# 20260908.net
KiCad netlist of a schematic drawn in Altium Designer
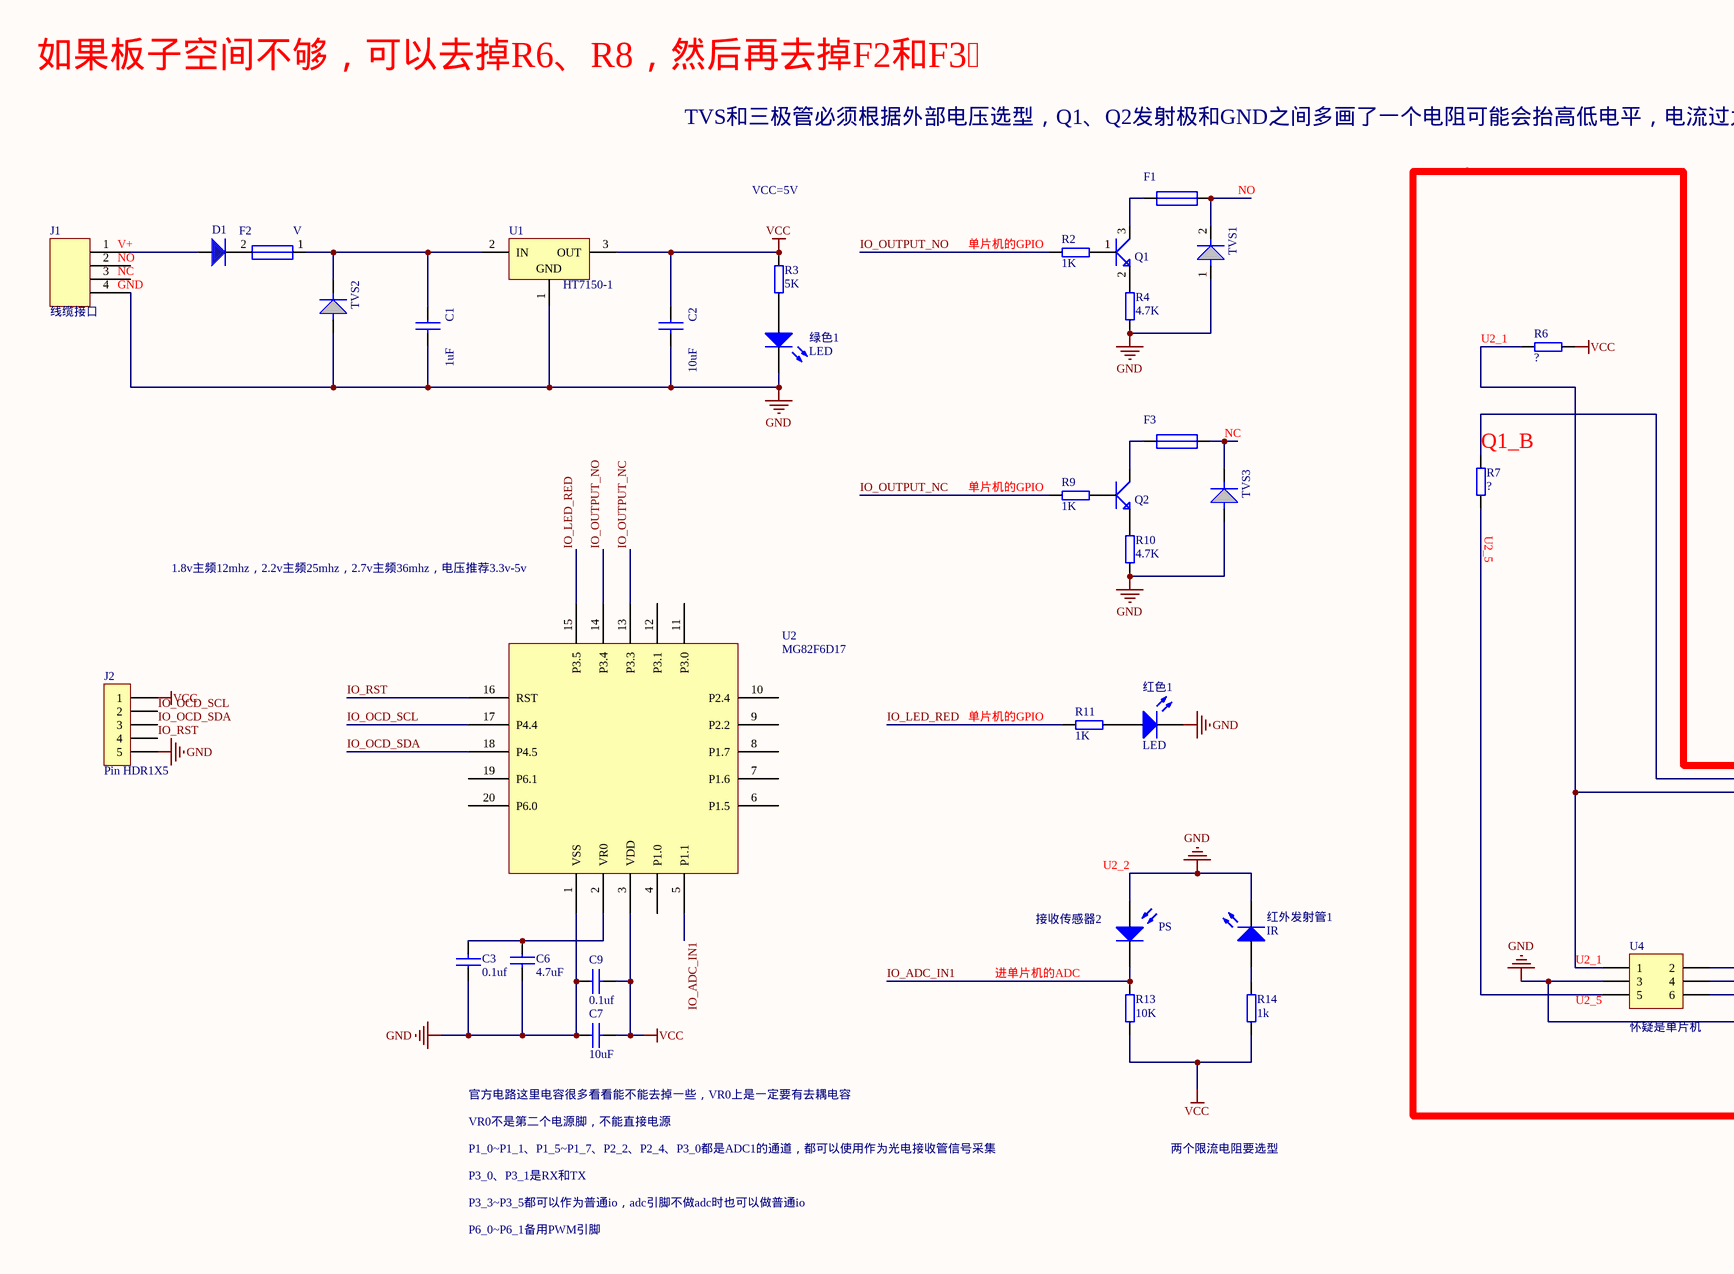
[diagram p0: 槽形开关原理图20260908.SchDoc, left]
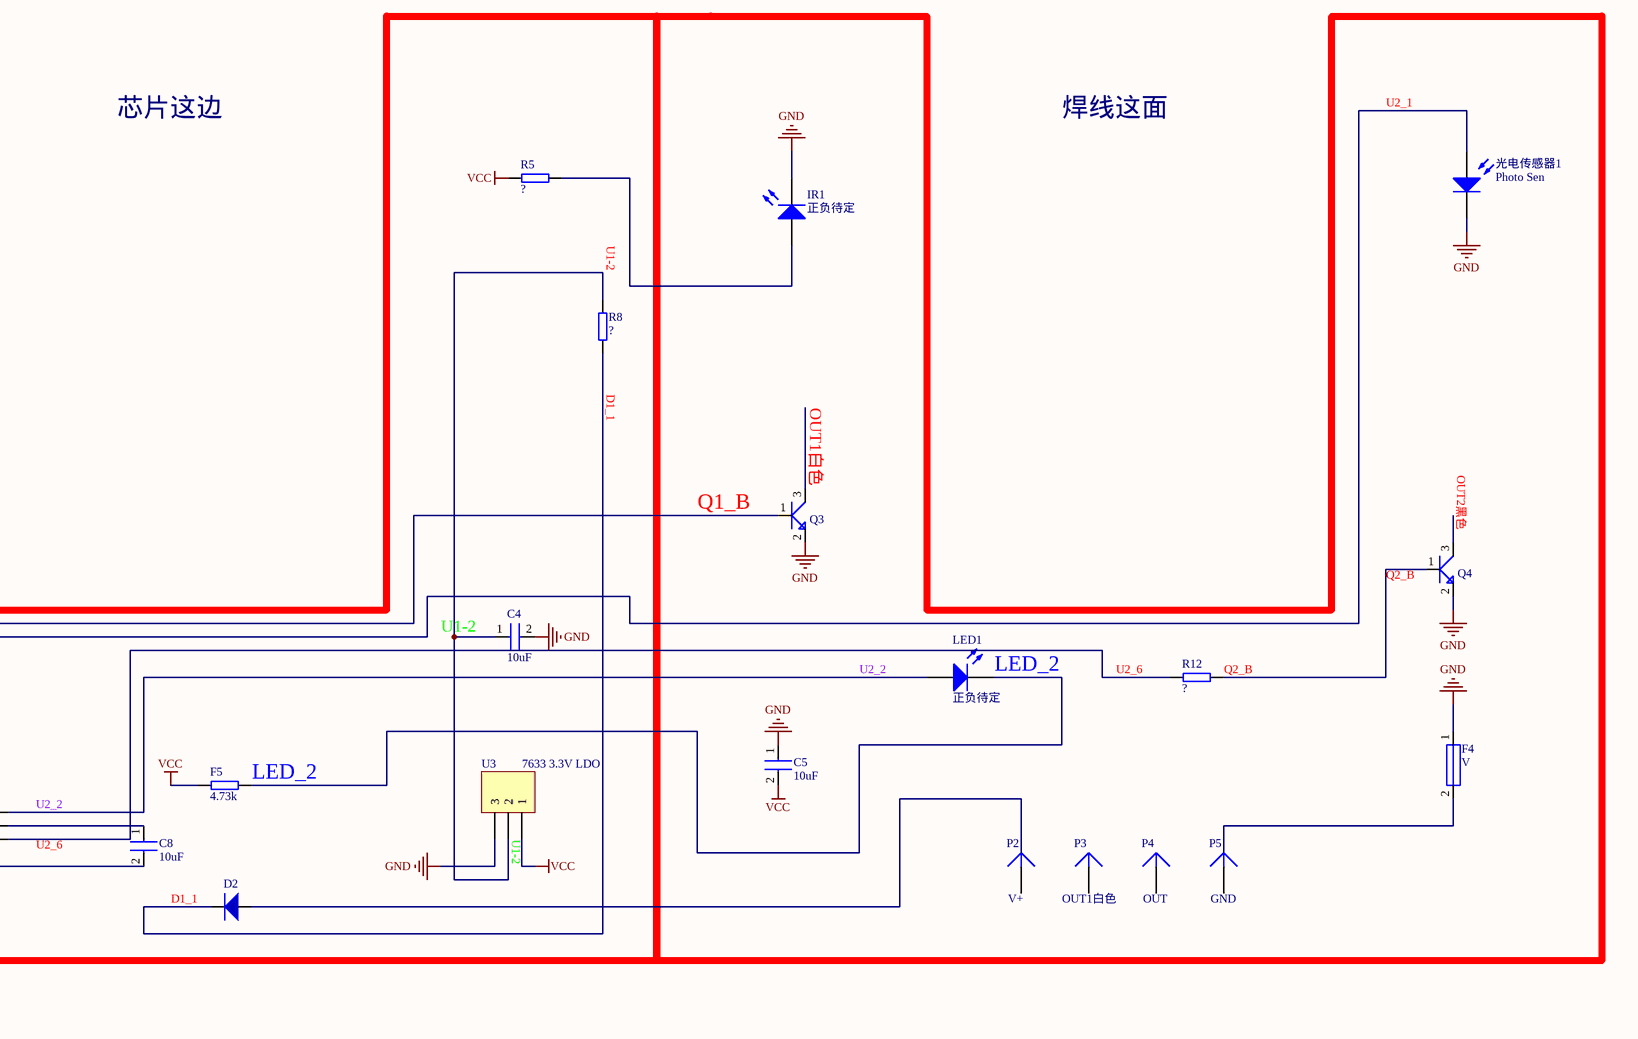
[diagram p1: 槽形开关原理图20260908.SchDoc, right]

(export (version "E")
  (design (tool "Eeschema 10.0.6"))
  (components
    (comp (ref "C1") (value "1uF") (footprint "1206") (libsource (lib "*") (part "CAP NP")))
    (comp (ref "C2") (value "10uF") (footprint "1206") (libsource (lib "*") (part "CAP NP")))
    (comp (ref "C3") (value "0.1uf") (footprint "1206") (libsource (lib "*") (part "CAP NP")))
    (comp (ref "C4") (value "10uF") (libsource (lib "*") (part "CAP")))
    (comp (ref "C5") (value "10uF") (libsource (lib "*") (part "CAP")))
    (comp (ref "C6") (value "4.7uF") (footprint "1206") (libsource (lib "*") (part "CAP NP")))
    (comp (ref "C7") (value "10uF") (footprint "1206") (libsource (lib "*") (part "CAP NP")))
    (comp (ref "C8") (value "10uF") (libsource (lib "*") (part "CAP")))
    (comp (ref "C9") (value "0.1uf") (footprint "1206") (libsource (lib "*") (part "CAP NP")))
    (comp (ref "D1") (value "~") (libsource (lib "*") (part "D")))
    (comp (ref "D2") (value "~") (libsource (lib "*") (part "D")))
    (comp (ref "F1") (value "V") (footprint "0805") (libsource (lib "") (part "FUSE_0_1")))
    (comp (ref "F2") (value "V") (footprint "0805") (libsource (lib "*") (part "FUSE_0")))
    (comp (ref "F3") (value "~") (footprint "0805") (libsource (lib "") (part "FUSE_0_1")))
    (comp (ref "F4") (value "V") (footprint "0805") (libsource (lib "") (part "FUSE_0_2")))
    (comp (ref "F5") (value "4.73k") (libsource (lib "*") (part "RES")))
    (comp (ref "IR1")
      (value "正负待定")
      (footprint "LED-0")
      (description "Typical INFRARED GaAs LED")
      (fields (field (name "PUBLISHER") "Altium Limited"))
      (libsource (lib "Miscellaneous Devices") (part "LED0"))
    )
    (comp (ref "J1") (value "线缆接口") (footprint "SIP4") (libsource (lib "*") (part "4H")))
    (comp (ref "J2")
      (value "Pin HDR1X5")
      (footprint "Pin HDR1X5/2mm-W")
      (libsource (lib "排针") (part "Pin HDR1X5"))
    )
    (comp (ref "LED1")
      (value "正负待定")
      (footprint "LED-0")
      (description "Typical INFRARED GaAs LED")
      (fields (field (name "PUBLISHER") "Altium Limited"))
      (libsource (lib "Miscellaneous Devices") (part "LED0"))
    )
    (comp (ref "P2")
      (value "V+")
      (footprint "PIN1")
      (description "Plug")
      (fields (field (name "PUBLISHER") "Altium Limited"))
      (libsource (lib "Miscellaneous Connectors") (part "Plug"))
    )
    (comp (ref "P3")
      (value "OUT1白色")
      (footprint "PIN1")
      (description "Plug")
      (fields (field (name "PUBLISHER") "Altium Limited"))
      (libsource (lib "Miscellaneous Connectors") (part "Plug"))
    )
    (comp (ref "P4")
      (value "OUT")
      (footprint "PIN1")
      (description "Plug")
      (fields (field (name "PUBLISHER") "Altium Limited"))
      (libsource (lib "Miscellaneous Connectors") (part "Plug"))
    )
    (comp (ref "P5")
      (value "GND")
      (footprint "PIN1")
      (description "Plug")
      (fields (field (name "PUBLISHER") "Altium Limited"))
      (libsource (lib "Miscellaneous Connectors") (part "Plug"))
    )
    (comp (ref "Q1") (value "2SC4617TLR") (libsource (lib "") (part "2SC4617_1")))
    (comp (ref "Q2") (value "2SC4617TLR") (libsource (lib "*") (part "2SC4617")))
    (comp (ref "Q3") (value "2SC4617TLR") (libsource (lib "") (part "2SC4617_1")))
    (comp (ref "Q4") (value "2SC4617TLR") (libsource (lib "") (part "2SC4617_1")))
    (comp (ref "R2") (value "1K") (libsource (lib "*") (part "RES")))
    (comp (ref "R3") (value "5K") (libsource (lib "*") (part "RES")))
    (comp (ref "R4") (value "4.7K") (libsource (lib "*") (part "RES")))
    (comp (ref "R5") (value "?") (libsource (lib "*") (part "RES")))
    (comp (ref "R6") (value "?") (libsource (lib "*") (part "RES")))
    (comp (ref "R7") (value "?") (libsource (lib "*") (part "RES")))
    (comp (ref "R8") (value "?") (libsource (lib "*") (part "RES")))
    (comp (ref "R9") (value "1K") (libsource (lib "*") (part "RES")))
    (comp (ref "R10") (value "4.7K") (libsource (lib "*") (part "RES")))
    (comp (ref "R11") (value "1K") (libsource (lib "*") (part "RES")))
    (comp (ref "R12") (value "?") (libsource (lib "*") (part "RES")))
    (comp (ref "R13") (value "10K") (libsource (lib "*") (part "RES")))
    (comp (ref "R14") (value "1k") (libsource (lib "*") (part "RES")))
    (comp (ref "TVS1") (value "~") (footprint "1206") (libsource (lib "") (part "D1N3063_0_1")))
    (comp (ref "TVS2") (value "M1") (footprint "1206") (libsource (lib "*") (part "D1N3063_0")))
    (comp (ref "TVS3") (value "~") (footprint "1206") (libsource (lib "*") (part "D1N3063_0")))
    (comp (ref "U1")
      (value "HT7150-1")
      (footprint "SOT89N")
      (description "3.0V 100mA Low Power,  Low Dropout Voltage (LDO) Regulator")
      (fields (field (name "PUBLISHER") "Altium Limited"))
      (libsource (lib "Holtek Power Mgt Voltage Regulator") (part "HT7530-1"))
    )
    (comp (ref "U2") (value "MG82F6D17") (libsource (lib "wwrDevice") (part "MG82F6D17 QFN20")))
    (comp (ref "U3")
      (value "7633 3.3V LDO")
      (footprint "HDR1X3")
      (description "Header, 3-Pin")
      (fields (field (name "PUBLISHER") "Altium Limited"))
      (libsource (lib "Miscellaneous Connectors") (part "Header 3"))
    )
    (comp (ref "U4")
      (value "怀疑是单片机")
      (footprint "HDR2X3")
      (description "Header, 3-Pin, Dual row")
      (fields (field (name "PUBLISHER") "Altium Limited"))
      (libsource (lib "Miscellaneous Connectors") (part "Header 3X2"))
    )
    (comp (ref "光电传感器1")
      (value "Photo Sen")
      (footprint "PIN2")
      (description "Photosensitive Diode")
      (fields (field (name "PUBLISHER") "Altium Limited"))
      (libsource (lib "Miscellaneous Devices") (part "Photo Sen"))
    )
    (comp (ref "接收传感器2")
      (value "PS")
      (footprint "PIN2")
      (description "Photosensitive Diode")
      (fields (field (name "PUBLISHER") "Altium Limited"))
      (libsource (lib "Miscellaneous Devices") (part "Photo Sen"))
    )
    (comp (ref "红外发射管1")
      (value "IR")
      (footprint "LED-0")
      (description "Typical INFRARED GaAs LED")
      (fields (field (name "PUBLISHER") "Altium Limited"))
      (libsource (lib "Miscellaneous Devices") (part "LED0"))
    )
    (comp (ref "红色1")
      (value "LED")
      (footprint "LED-0")
      (description "Typical INFRARED GaAs LED")
      (fields (field (name "PUBLISHER") "Altium Limited"))
      (libsource (lib "Miscellaneous Devices") (part "LED0"))
    )
    (comp (ref "绿色1")
      (value "LED")
      (footprint "LED-0")
      (description "Typical INFRARED GaAs LED")
      (fields (field (name "PUBLISHER") "Altium Limited"))
      (libsource (lib "Miscellaneous Devices") (part "LED0"))
    )
  )
  (nets
    (net (code "1") (name "/IO_ADC_IN1") (class "Default")
      (node (ref "R13") (pin "2") (pinfunction "2_2") (pintype "passive"))
      (node (ref "U2") (pin "5") (pinfunction "P1.1_5") (pintype "passive"))
      (node (ref "接收传感器2") (pin "2") (pinfunction "K_2") (pintype "passive"))
    )
    (net (code "2") (name "/IO_LED_RED") (class "Default")
      (node (ref "R11") (pin "1") (pinfunction "1_1") (pintype "passive"))
      (node (ref "U2") (pin "15") (pinfunction "P3.5_15") (pintype "passive"))
    )
    (net (code "3") (name "/IO_OCD_SCL") (class "Default")
      (node (ref "J2") (pin "2") (pinfunction "2_2") (pintype "passive"))
      (node (ref "U2") (pin "17") (pinfunction "P4.4_17") (pintype "passive"))
    )
    (net (code "4") (name "/IO_OCD_SDA") (class "Default")
      (node (ref "J2") (pin "3") (pinfunction "3_3") (pintype "passive"))
      (node (ref "U2") (pin "18") (pinfunction "P4.5_18") (pintype "passive"))
    )
    (net (code "5") (name "/IO_OUTPUT_NC") (class "Default")
      (node (ref "R9") (pin "1") (pinfunction "1_1") (pintype "passive"))
      (node (ref "U2") (pin "13") (pinfunction "P3.3_13") (pintype "passive"))
    )
    (net (code "6") (name "/IO_OUTPUT_NO") (class "Default")
      (node (ref "R2") (pin "1") (pinfunction "1_1") (pintype "passive"))
      (node (ref "U2") (pin "14") (pinfunction "P3.4_14") (pintype "passive"))
    )
    (net (code "7") (name "/IO_RST") (class "Default")
      (node (ref "J2") (pin "4") (pinfunction "4_4") (pintype "passive"))
      (node (ref "U2") (pin "16") (pinfunction "RST_16") (pintype "passive"))
    )
    (net (code "8") (name "GND") (class "Default")
      (node (ref "C1") (pin "2") (pinfunction "2_2") (pintype "passive"))
      (node (ref "C2") (pin "2") (pinfunction "2_2") (pintype "passive"))
      (node (ref "C3") (pin "1") (pinfunction "1_1") (pintype "passive"))
      (node (ref "C4") (pin "2") (pintype "passive"))
      (node (ref "C5") (pin "1") (pintype "passive"))
      (node (ref "C6") (pin "2") (pinfunction "2_2") (pintype "passive"))
      (node (ref "C7") (pin "1") (pinfunction "1_1") (pintype "passive"))
      (node (ref "C8") (pin "2") (pintype "passive"))
      (node (ref "C9") (pin "1") (pinfunction "1_1") (pintype "passive"))
      (node (ref "F4") (pin "1") (pinfunction "1_1") (pintype "passive"))
      (node (ref "IR1") (pin "2") (pinfunction "K_2") (pintype "passive"))
      (node (ref "J1") (pin "4") (pintype "passive"))
      (node (ref "J2") (pin "5") (pinfunction "5_5") (pintype "passive"))
      (node (ref "Q3") (pin "2") (pinfunction "E_2") (pintype "passive"))
      (node (ref "Q4") (pin "2") (pinfunction "E_2") (pintype "passive"))
      (node (ref "R10") (pin "2") (pinfunction "2_2") (pintype "passive"))
      (node (ref "R4") (pin "2") (pinfunction "2_2") (pintype "passive"))
      (node (ref "TVS1") (pin "1") (pinfunction "1_1") (pintype "passive"))
      (node (ref "TVS2") (pin "1") (pinfunction "1_1") (pintype "passive"))
      (node (ref "TVS3") (pin "1") (pinfunction "1_1") (pintype "passive"))
      (node (ref "U1") (pin "1") (pinfunction "GND_1") (pintype "power_in"))
      (node (ref "U2") (pin "1") (pinfunction "VSS_1") (pintype "passive"))
      (node (ref "U3") (pin "3") (pinfunction "3_3") (pintype "passive"))
      (node (ref "U4") (pin "3") (pinfunction "3_3") (pintype "passive"))
      (node (ref "光电传感器1") (pin "2") (pinfunction "K_2") (pintype "passive"))
      (node (ref "接收传感器2") (pin "1") (pinfunction "A_1") (pintype "passive"))
      (node (ref "红外发射管1") (pin "2") (pinfunction "K_2") (pintype "passive"))
      (node (ref "红色1") (pin "2") (pinfunction "K_2") (pintype "passive"))
      (node (ref "绿色1") (pin "2") (pinfunction "K_2") (pintype "passive"))
    )
    (net (code "9") (name "Net-(C4-Pad1)") (class "Default")
      (node (ref "C4") (pin "1") (pintype "passive"))
      (node (ref "R8") (pin "2") (pinfunction "2_2") (pintype "passive"))
      (node (ref "U3") (pin "2") (pinfunction "2_2") (pintype "passive"))
    )
    (net (code "10") (name "Net-(C8-Pad1)") (class "Default")
      (node (ref "C8") (pin "1") (pintype "passive"))
      (node (ref "U4") (pin "4") (pinfunction "4_4") (pintype "passive"))
    )
    (net (code "11") (name "Net-(D1-Pad1)") (class "Default")
      (node (ref "D1") (pin "1") (pintype "passive"))
      (node (ref "J1") (pin "1") (pintype "passive"))
    )
    (net (code "12") (name "Net-(D1-Pad2)") (class "Default")
      (node (ref "D1") (pin "2") (pintype "passive"))
      (node (ref "F2") (pin "2") (pinfunction "2_2") (pintype "passive"))
    )
    (net (code "13") (name "Net-(D2-Pad2)") (class "Default")
      (node (ref "D2") (pin "2") (pintype "passive"))
      (node (ref "R8") (pin "1") (pinfunction "1_1") (pintype "passive"))
    )
    (net (code "14") (name "Net-(F1-Pad1)") (class "Default")
      (node (ref "F1") (pin "1") (pinfunction "1_1") (pintype "passive"))
      (node (ref "TVS1") (pin "2") (pinfunction "2_2") (pintype "passive"))
    )
    (net (code "15") (name "Net-(F3-Pad1)") (class "Default")
      (node (ref "F3") (pin "1") (pinfunction "1_1") (pintype "passive"))
      (node (ref "TVS3") (pin "2") (pinfunction "2_2") (pintype "passive"))
    )
    (net (code "16") (name "Net-(IR1-A)") (class "Default")
      (node (ref "IR1") (pin "1") (pinfunction "A_1") (pintype "passive"))
      (node (ref "R5") (pin "1") (pinfunction "1_1") (pintype "passive"))
    )
    (net (code "17") (name "Net-(LED1-A)") (class "Default")
      (node (ref "LED1") (pin "1") (pinfunction "A_1") (pintype "passive"))
      (node (ref "U4") (pin "2") (pinfunction "2_2") (pintype "passive"))
    )
    (net (code "18") (name "Net-(LED1-K)") (class "Default")
      (node (ref "F5") (pin "1") (pinfunction "1_1") (pintype "passive"))
      (node (ref "LED1") (pin "2") (pinfunction "K_2") (pintype "passive"))
    )
    (net (code "19") (name "Net-(Q1-B)") (class "Default")
      (node (ref "Q1") (pin "1") (pinfunction "B_1") (pintype "passive"))
      (node (ref "R2") (pin "2") (pinfunction "2_2") (pintype "passive"))
    )
    (net (code "20") (name "Net-(Q1-C)") (class "Default")
      (node (ref "F1") (pin "2") (pinfunction "2_2") (pintype "passive"))
      (node (ref "Q1") (pin "3") (pinfunction "C_3") (pintype "passive"))
    )
    (net (code "21") (name "Net-(Q1-E)") (class "Default")
      (node (ref "Q1") (pin "2") (pinfunction "E_2") (pintype "passive"))
      (node (ref "R4") (pin "1") (pinfunction "1_1") (pintype "passive"))
    )
    (net (code "22") (name "Net-(Q2-B)") (class "Default")
      (node (ref "Q2") (pin "1") (pinfunction "B_1") (pintype "passive"))
      (node (ref "R9") (pin "2") (pinfunction "2_2") (pintype "passive"))
    )
    (net (code "23") (name "Net-(Q2-C)") (class "Default")
      (node (ref "F3") (pin "2") (pinfunction "2_2") (pintype "passive"))
      (node (ref "Q2") (pin "3") (pinfunction "C_3") (pintype "passive"))
    )
    (net (code "24") (name "Net-(Q2-E)") (class "Default")
      (node (ref "Q2") (pin "2") (pinfunction "E_2") (pintype "passive"))
      (node (ref "R10") (pin "1") (pinfunction "1_1") (pintype "passive"))
    )
    (net (code "25") (name "Net-(Q3-B)") (class "Default")
      (node (ref "Q3") (pin "1") (pinfunction "B_1") (pintype "passive"))
      (node (ref "R7") (pin "2") (pinfunction "2_2") (pintype "passive"))
    )
    (net (code "26") (name "Net-(Q4-B)") (class "Default")
      (node (ref "Q4") (pin "1") (pinfunction "B_1") (pintype "passive"))
      (node (ref "R12") (pin "1") (pinfunction "1_1") (pintype "passive"))
    )
    (net (code "27") (name "Net-(R7-Pad1)") (class "Default")
      (node (ref "R7") (pin "1") (pinfunction "1_1") (pintype "passive"))
      (node (ref "U4") (pin "5") (pinfunction "5_5") (pintype "passive"))
    )
    (net (code "28") (name "Net-(R12-Pad2)") (class "Default")
      (node (ref "R12") (pin "2") (pinfunction "2_2") (pintype "passive"))
      (node (ref "U4") (pin "6") (pinfunction "6_6") (pintype "passive"))
    )
    (net (code "29") (name "Net-(U1-IN)") (class "Default")
      (node (ref "C1") (pin "1") (pinfunction "1_1") (pintype "passive"))
      (node (ref "F2") (pin "1") (pinfunction "1_1") (pintype "passive"))
      (node (ref "TVS2") (pin "2") (pinfunction "2_2") (pintype "passive"))
      (node (ref "U1") (pin "2") (pinfunction "IN_2") (pintype "power_in"))
    )
    (net (code "30") (name "Net-(U2-VR0)") (class "Default")
      (node (ref "C3") (pin "2") (pinfunction "2_2") (pintype "passive"))
      (node (ref "C6") (pin "1") (pinfunction "1_1") (pintype "passive"))
      (node (ref "U2") (pin "2") (pinfunction "VR0_2") (pintype "passive"))
    )
    (net (code "31") (name "Net-(光电传感器1-A)") (class "Default")
      (node (ref "R6") (pin "2") (pinfunction "2_2") (pintype "passive"))
      (node (ref "U4") (pin "1") (pinfunction "1_1") (pintype "passive"))
      (node (ref "光电传感器1") (pin "1") (pinfunction "A_1") (pintype "passive"))
    )
    (net (code "32") (name "Net-(红外发射管1-A)") (class "Default")
      (node (ref "R14") (pin "2") (pinfunction "2_2") (pintype "passive"))
      (node (ref "红外发射管1") (pin "1") (pinfunction "A_1") (pintype "passive"))
    )
    (net (code "33") (name "Net-(红色1-A)") (class "Default")
      (node (ref "R11") (pin "2") (pinfunction "2_2") (pintype "passive"))
      (node (ref "红色1") (pin "1") (pinfunction "A_1") (pintype "passive"))
    )
    (net (code "34") (name "Net-(绿色1-A)") (class "Default")
      (node (ref "R3") (pin "2") (pinfunction "2_2") (pintype "passive"))
      (node (ref "绿色1") (pin "1") (pinfunction "A_1") (pintype "passive"))
    )
    (net (code "35") (name "VCC") (class "Default")
      (node (ref "C2") (pin "1") (pinfunction "1_1") (pintype "passive"))
      (node (ref "C5") (pin "2") (pintype "passive"))
      (node (ref "C7") (pin "2") (pinfunction "2_2") (pintype "passive"))
      (node (ref "C9") (pin "2") (pinfunction "2_2") (pintype "passive"))
      (node (ref "F5") (pin "2") (pinfunction "2_2") (pintype "passive"))
      (node (ref "J2") (pin "1") (pinfunction "1_1") (pintype "passive"))
      (node (ref "R13") (pin "1") (pinfunction "1_1") (pintype "passive"))
      (node (ref "R14") (pin "1") (pinfunction "1_1") (pintype "passive"))
      (node (ref "R3") (pin "1") (pinfunction "1_1") (pintype "passive"))
      (node (ref "R5") (pin "2") (pinfunction "2_2") (pintype "passive"))
      (node (ref "R6") (pin "1") (pinfunction "1_1") (pintype "passive"))
      (node (ref "U1") (pin "3") (pinfunction "OUT_3") (pintype "power_in"))
      (node (ref "U2") (pin "3") (pinfunction "VDD_3") (pintype "passive"))
      (node (ref "U3") (pin "1") (pinfunction "1_1") (pintype "passive"))
    )
    (net (code "36") (name "unconnected-(D2-Pad1)") (class "Default")
      (node (ref "D2") (pin "1") (pintype "passive"))
    )
    (net (code "37") (name "unconnected-(F4-Pad2)") (class "Default")
      (node (ref "F4") (pin "2") (pinfunction "2_2") (pintype "passive"))
    )
    (net (code "38") (name "unconnected-(J1-Pad2)") (class "Default")
      (node (ref "J1") (pin "2") (pintype "passive"))
    )
    (net (code "39") (name "unconnected-(J1-Pad3)") (class "Default")
      (node (ref "J1") (pin "3") (pintype "passive"))
    )
    (net (code "40") (name "unconnected-(P2-Pad1)") (class "Default")
      (node (ref "P2") (pin "1") (pinfunction "1_1") (pintype "passive"))
    )
    (net (code "41") (name "unconnected-(P3-Pad1)") (class "Default")
      (node (ref "P3") (pin "1") (pinfunction "1_1") (pintype "passive"))
    )
    (net (code "42") (name "unconnected-(P4-Pad1)") (class "Default")
      (node (ref "P4") (pin "1") (pinfunction "1_1") (pintype "passive"))
    )
    (net (code "43") (name "unconnected-(P5-Pad1)") (class "Default")
      (node (ref "P5") (pin "1") (pinfunction "1_1") (pintype "passive"))
    )
    (net (code "44") (name "unconnected-(Q3-C-Pad3)") (class "Default")
      (node (ref "Q3") (pin "3") (pinfunction "C_3") (pintype "passive"))
    )
    (net (code "45") (name "unconnected-(Q4-C-Pad3)") (class "Default")
      (node (ref "Q4") (pin "3") (pinfunction "C_3") (pintype "passive"))
    )
    (net (code "46") (name "unconnected-(U2-P1.0-Pad4)") (class "Default")
      (node (ref "U2") (pin "4") (pinfunction "P1.0_4") (pintype "passive"))
    )
    (net (code "47") (name "unconnected-(U2-P1.5-Pad6)") (class "Default")
      (node (ref "U2") (pin "6") (pinfunction "P1.5_6") (pintype "passive"))
    )
    (net (code "48") (name "unconnected-(U2-P1.6-Pad7)") (class "Default")
      (node (ref "U2") (pin "7") (pinfunction "P1.6_7") (pintype "passive"))
    )
    (net (code "49") (name "unconnected-(U2-P1.7-Pad8)") (class "Default")
      (node (ref "U2") (pin "8") (pinfunction "P1.7_8") (pintype "passive"))
    )
    (net (code "50") (name "unconnected-(U2-P2.2-Pad9)") (class "Default")
      (node (ref "U2") (pin "9") (pinfunction "P2.2_9") (pintype "passive"))
    )
    (net (code "51") (name "unconnected-(U2-P2.4-Pad10)") (class "Default")
      (node (ref "U2") (pin "10") (pinfunction "P2.4_10") (pintype "passive"))
    )
    (net (code "52") (name "unconnected-(U2-P3.0-Pad11)") (class "Default")
      (node (ref "U2") (pin "11") (pinfunction "P3.0_11") (pintype "passive"))
    )
    (net (code "53") (name "unconnected-(U2-P3.1-Pad12)") (class "Default")
      (node (ref "U2") (pin "12") (pinfunction "P3.1_12") (pintype "passive"))
    )
    (net (code "54") (name "unconnected-(U2-P6.0-Pad20)") (class "Default")
      (node (ref "U2") (pin "20") (pinfunction "P6.0_20") (pintype "passive"))
    )
    (net (code "55") (name "unconnected-(U2-P6.1-Pad19)") (class "Default")
      (node (ref "U2") (pin "19") (pinfunction "P6.1_19") (pintype "passive"))
    )
  )
)
